# Ex_EEPROM.net
KiCad netlist of a schematic drawn in EAGLE
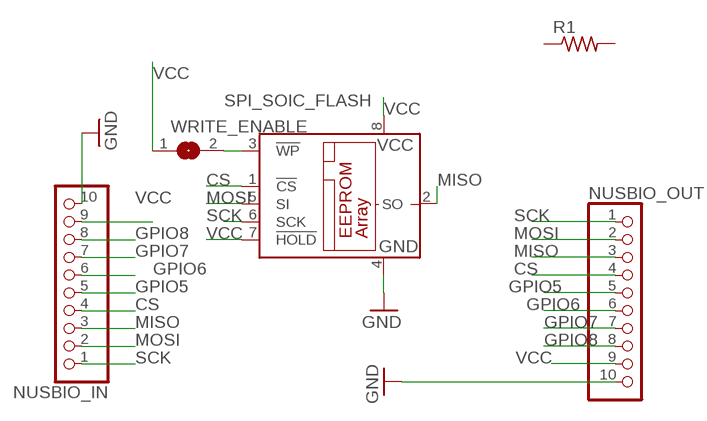
[diagram p0: schematic, sheet 1]

(export (version "E")
  (design (tool "Eeschema 10.0.6"))
  (components
    (comp (ref "NUSBIO_IN")
      (value "PINHD-1X10")
      (footprint "eagle-import:1X10-BIG")
      (libsource (lib "eagle-import") (part "PINHD-1X10"))
    )
    (comp (ref "NUSBIO_OUT")
      (value "PINHD-1X10")
      (footprint "eagle-import:1X10-BIG")
      (libsource (lib "eagle-import") (part "PINHD-1X10"))
    )
    (comp (ref "R1")
      (value "R-US_R1206")
      (footprint "eagle-import:R1206")
      (libsource (lib "eagle-import") (part "R-US_R1206"))
    )
    (comp (ref "SPI_SOIC_FLASH")
      (value "25AA080SN")
      (footprint "eagle-import:SO-08")
      (fields (field (name "MF") "MICROCHIP") (field (name "MPN") "25AA080/SN"))
      (libsource (lib "eagle-import") (part "25SNAA080"))
    )
    (comp (ref "WRITE_ENABLE")
      (value "SOLDERJUMPERREFLOW")
      (footprint "eagle-import:SOLDERJUMPER_REFLOW")
      (libsource (lib "eagle-import") (part "SOLDERJUMPERREFLOW"))
    )
  )
  (nets
    (net (code "1") (name "/CS") (class "Default")
      (node (ref "NUSBIO_IN") (pin "4") (pinfunction "4_4") (pintype "passive"))
      (node (ref "NUSBIO_OUT") (pin "4") (pinfunction "4_4") (pintype "passive"))
      (node (ref "SPI_SOIC_FLASH") (pin "1") (pinfunction "~{CS}_1") (pintype "input"))
    )
    (net (code "2") (name "/GPIO5") (class "Default")
      (node (ref "NUSBIO_IN") (pin "5") (pinfunction "5_5") (pintype "passive"))
      (node (ref "NUSBIO_OUT") (pin "5") (pinfunction "5_5") (pintype "passive"))
    )
    (net (code "3") (name "/GPIO6") (class "Default")
      (node (ref "NUSBIO_IN") (pin "6") (pinfunction "6_6") (pintype "passive"))
      (node (ref "NUSBIO_OUT") (pin "6") (pinfunction "6_6") (pintype "passive"))
    )
    (net (code "4") (name "/GPIO7") (class "Default")
      (node (ref "NUSBIO_IN") (pin "7") (pinfunction "7_7") (pintype "passive"))
      (node (ref "NUSBIO_OUT") (pin "7") (pinfunction "7_7") (pintype "passive"))
    )
    (net (code "5") (name "/GPIO8") (class "Default")
      (node (ref "NUSBIO_IN") (pin "8") (pinfunction "8_8") (pintype "passive"))
      (node (ref "NUSBIO_OUT") (pin "8") (pinfunction "8_8") (pintype "passive"))
    )
    (net (code "6") (name "/MISO") (class "Default")
      (node (ref "NUSBIO_IN") (pin "3") (pinfunction "3_3") (pintype "passive"))
      (node (ref "NUSBIO_OUT") (pin "3") (pinfunction "3_3") (pintype "passive"))
      (node (ref "SPI_SOIC_FLASH") (pin "2") (pinfunction "SO_2") (pintype "bidirectional"))
    )
    (net (code "7") (name "/MOSI") (class "Default")
      (node (ref "NUSBIO_IN") (pin "2") (pinfunction "2_2") (pintype "passive"))
      (node (ref "NUSBIO_OUT") (pin "2") (pinfunction "2_2") (pintype "passive"))
      (node (ref "SPI_SOIC_FLASH") (pin "5") (pinfunction "SI_5") (pintype "input"))
    )
    (net (code "8") (name "/SCK") (class "Default")
      (node (ref "NUSBIO_IN") (pin "1") (pinfunction "1_1") (pintype "passive"))
      (node (ref "NUSBIO_OUT") (pin "1") (pinfunction "1_1") (pintype "passive"))
      (node (ref "SPI_SOIC_FLASH") (pin "6") (pinfunction "SCK_6") (pintype "input"))
    )
    (net (code "9") (name "/VCC") (class "Default")
      (node (ref "NUSBIO_IN") (pin "9") (pinfunction "9_9") (pintype "passive"))
      (node (ref "NUSBIO_OUT") (pin "9") (pinfunction "9_9") (pintype "passive"))
      (node (ref "SPI_SOIC_FLASH") (pin "7") (pinfunction "~{HOLD}_7") (pintype "input"))
      (node (ref "SPI_SOIC_FLASH") (pin "8") (pinfunction "VCC_8") (pintype "power_in"))
      (node (ref "WRITE_ENABLE") (pin "1") (pinfunction "1_1") (pintype "passive"))
    )
    (net (code "10") (name "GND") (class "Default")
      (node (ref "NUSBIO_IN") (pin "10") (pinfunction "10_10") (pintype "passive"))
      (node (ref "NUSBIO_OUT") (pin "10") (pinfunction "10_10") (pintype "passive"))
      (node (ref "SPI_SOIC_FLASH") (pin "4") (pinfunction "GND_4") (pintype "power_in"))
    )
    (net (code "11") (name "Net-(SPI_SOIC_FLASH-~{WP})") (class "Default")
      (node (ref "SPI_SOIC_FLASH") (pin "3") (pinfunction "~{WP}_3") (pintype "input"))
      (node (ref "WRITE_ENABLE") (pin "2") (pinfunction "2_2") (pintype "passive"))
    )
    (net (code "12") (name "unconnected-(R1-Pad1)") (class "Default")
      (node (ref "R1") (pin "1") (pinfunction "1_1") (pintype "passive"))
    )
    (net (code "13") (name "unconnected-(R1-Pad2)") (class "Default")
      (node (ref "R1") (pin "2") (pinfunction "2_2") (pintype "passive"))
    )
  )
)
